# PLT-01-RevD.net
KiCad netlist of a schematic drawn in EAGLE
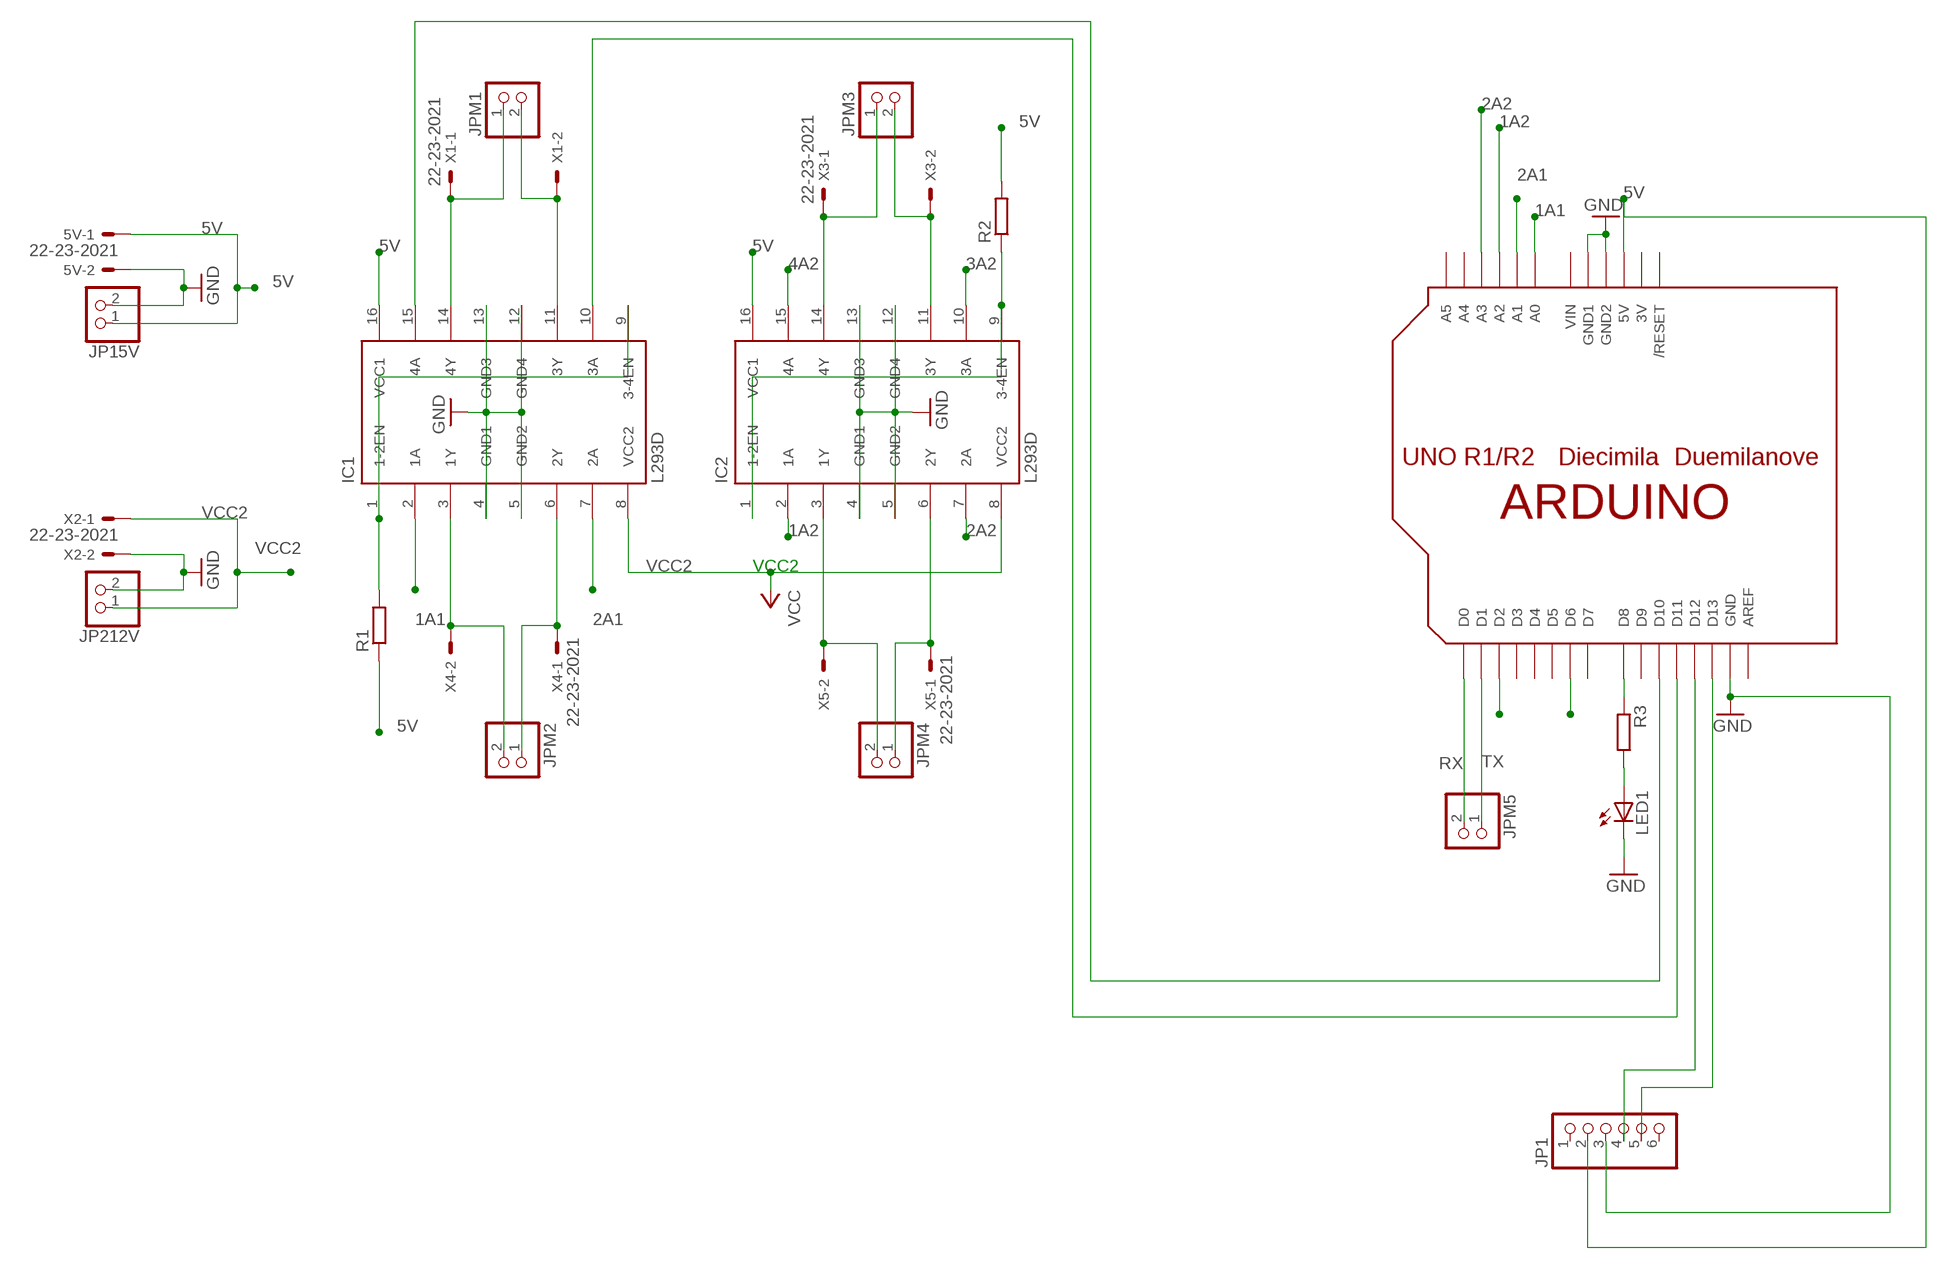
[diagram p0: schematic, sheet 1]

(export (version "E")
  (design (tool "Eeschema 10.0.6"))
  (components
    (comp (ref "5V")
      (value "22-23-2021")
      (footprint "eagle-import:22-23-2021")
      (fields (field (name "MF") "MOLEX"))
      (libsource (lib "eagle-import") (part "22-23-2021"))
    )
    (comp (ref "IC1")
      (value "L293D")
      (footprint "eagle-import:DIL16")
      (libsource (lib "eagle-import") (part "L293D"))
    )
    (comp (ref "IC2")
      (value "L293D")
      (footprint "eagle-import:DIL16")
      (libsource (lib "eagle-import") (part "L293D"))
    )
    (comp (ref "JP1")
      (value "PINHD-1X6")
      (footprint "eagle-import:1X06")
      (libsource (lib "eagle-import") (part "PINHD-1X6"))
    )
    (comp (ref "JP15V")
      (value "PINHD-1X2")
      (footprint "eagle-import:1X02")
      (libsource (lib "eagle-import") (part "PINHD-1X2"))
    )
    (comp (ref "JP212V")
      (value "PINHD-1X2")
      (footprint "eagle-import:1X02")
      (libsource (lib "eagle-import") (part "PINHD-1X2"))
    )
    (comp (ref "JPM1")
      (value "PINHD-1X2")
      (footprint "eagle-import:1X02")
      (libsource (lib "eagle-import") (part "PINHD-1X2"))
    )
    (comp (ref "JPM2")
      (value "PINHD-1X2")
      (footprint "eagle-import:1X02")
      (libsource (lib "eagle-import") (part "PINHD-1X2"))
    )
    (comp (ref "JPM3")
      (value "PINHD-1X2")
      (footprint "eagle-import:1X02")
      (libsource (lib "eagle-import") (part "PINHD-1X2"))
    )
    (comp (ref "JPM4")
      (value "PINHD-1X2")
      (footprint "eagle-import:1X02")
      (libsource (lib "eagle-import") (part "PINHD-1X2"))
    )
    (comp (ref "JPM5")
      (value "PINHD-1X2")
      (footprint "eagle-import:1X02")
      (libsource (lib "eagle-import") (part "PINHD-1X2"))
    )
    (comp (ref "LED1")
      (value "LED5MM")
      (footprint "eagle-import:LED5MM")
      (libsource (lib "eagle-import") (part "LED5MM"))
    )
    (comp (ref "R1")
      (value "R-EU_0207/10")
      (footprint "eagle-import:0207_10")
      (libsource (lib "eagle-import") (part "R-EU_0207/10"))
    )
    (comp (ref "R2")
      (value "R-EU_0207/10")
      (footprint "eagle-import:0207_10")
      (libsource (lib "eagle-import") (part "R-EU_0207/10"))
    )
    (comp (ref "R3")
      (value "R-EU_0207/10")
      (footprint "eagle-import:0207_10")
      (libsource (lib "eagle-import") (part "R-EU_0207/10"))
    )
    (comp (ref "U$1")
      (value "ARDUINOUNO")
      (footprint "eagle-import:ARDUINO")
      (libsource (lib "eagle-import") (part "ARDUINOUNO"))
    )
    (comp (ref "X1")
      (value "22-23-2021")
      (footprint "eagle-import:22-23-2021")
      (fields (field (name "MF") "MOLEX"))
      (libsource (lib "eagle-import") (part "22-23-2021"))
    )
    (comp (ref "X2")
      (value "22-23-2021")
      (footprint "eagle-import:22-23-2021")
      (fields (field (name "MF") "MOLEX"))
      (libsource (lib "eagle-import") (part "22-23-2021"))
    )
    (comp (ref "X3")
      (value "22-23-2021")
      (footprint "eagle-import:22-23-2021")
      (fields (field (name "MF") "MOLEX"))
      (libsource (lib "eagle-import") (part "22-23-2021"))
    )
    (comp (ref "X4")
      (value "22-23-2021")
      (footprint "eagle-import:22-23-2021")
      (fields (field (name "MF") "MOLEX"))
      (libsource (lib "eagle-import") (part "22-23-2021"))
    )
    (comp (ref "X5")
      (value "22-23-2021")
      (footprint "eagle-import:22-23-2021")
      (fields (field (name "MF") "MOLEX"))
      (libsource (lib "eagle-import") (part "22-23-2021"))
    )
  )
  (nets
    (net (code "1") (name "/1A1") (class "Default")
      (node (ref "IC1") (pin "2") (pinfunction "1A_2") (pintype "input"))
      (node (ref "U$1") (pin "A0") (pinfunction "A0_A0") (pintype "bidirectional"))
    )
    (net (code "2") (name "/1A2") (class "Default")
      (node (ref "IC2") (pin "2") (pinfunction "1A_2") (pintype "input"))
      (node (ref "U$1") (pin "A2") (pinfunction "A2_A2") (pintype "bidirectional"))
    )
    (net (code "3") (name "/2A1") (class "Default")
      (node (ref "IC1") (pin "7") (pinfunction "2A_7") (pintype "input"))
      (node (ref "U$1") (pin "A1") (pinfunction "A1_A1") (pintype "bidirectional"))
    )
    (net (code "4") (name "/2A2") (class "Default")
      (node (ref "IC2") (pin "7") (pinfunction "2A_7") (pintype "input"))
      (node (ref "U$1") (pin "A3") (pinfunction "A3_A3") (pintype "bidirectional"))
    )
    (net (code "5") (name "/3A2") (class "Default")
      (node (ref "IC2") (pin "10") (pinfunction "3A_10") (pintype "input"))
      (node (ref "U$1") (pin "D2") (pinfunction "D2_D2") (pintype "bidirectional"))
    )
    (net (code "6") (name "/3V") (class "Default")
      (node (ref "U$1") (pin "3V") (pinfunction "3V_3V") (pintype "power_in"))
    )
    (net (code "7") (name "/4A2") (class "Default")
      (node (ref "IC2") (pin "15") (pinfunction "4A_15") (pintype "input"))
      (node (ref "U$1") (pin "D6") (pinfunction "D6_D6") (pintype "bidirectional"))
    )
    (net (code "8") (name "/5V") (class "Default")
      (node (ref "5V") (pin "1") (pinfunction "S_1") (pintype "passive"))
      (node (ref "IC1") (pin "16") (pinfunction "VCC1_16") (pintype "power_in"))
      (node (ref "IC2") (pin "16") (pinfunction "VCC1_16") (pintype "power_in"))
      (node (ref "JP1") (pin "2") (pinfunction "2_2") (pintype "passive"))
      (node (ref "JP15V") (pin "1") (pinfunction "1_1") (pintype "passive"))
      (node (ref "R1") (pin "1") (pinfunction "1_1") (pintype "passive"))
      (node (ref "R2") (pin "2") (pinfunction "2_2") (pintype "passive"))
      (node (ref "U$1") (pin "5V") (pinfunction "5V_5V") (pintype "power_in"))
    )
    (net (code "9") (name "/RX") (class "Default")
      (node (ref "JPM5") (pin "2") (pinfunction "2_2") (pintype "passive"))
      (node (ref "U$1") (pin "D0") (pinfunction "D0_D0") (pintype "bidirectional"))
    )
    (net (code "10") (name "/TX") (class "Default")
      (node (ref "JPM5") (pin "1") (pinfunction "1_1") (pintype "passive"))
      (node (ref "U$1") (pin "D1") (pinfunction "D1_D1") (pintype "bidirectional"))
    )
    (net (code "11") (name "/VIN") (class "Default")
      (node (ref "U$1") (pin "VIN") (pinfunction "VIN_VIN") (pintype "power_in"))
    )
    (net (code "12") (name "GND") (class "Default")
      (node (ref "5V") (pin "2") (pinfunction "S_2") (pintype "passive"))
      (node (ref "IC1") (pin "12") (pinfunction "GND4_12") (pintype "power_in"))
      (node (ref "IC1") (pin "13") (pinfunction "GND3_13") (pintype "power_in"))
      (node (ref "IC1") (pin "4") (pinfunction "GND1_4") (pintype "power_in"))
      (node (ref "IC1") (pin "5") (pinfunction "GND2_5") (pintype "power_in"))
      (node (ref "IC2") (pin "12") (pinfunction "GND4_12") (pintype "power_in"))
      (node (ref "IC2") (pin "13") (pinfunction "GND3_13") (pintype "power_in"))
      (node (ref "IC2") (pin "4") (pinfunction "GND1_4") (pintype "power_in"))
      (node (ref "IC2") (pin "5") (pinfunction "GND2_5") (pintype "power_in"))
      (node (ref "JP1") (pin "3") (pinfunction "3_3") (pintype "passive"))
      (node (ref "JP15V") (pin "2") (pinfunction "2_2") (pintype "passive"))
      (node (ref "JP212V") (pin "2") (pinfunction "2_2") (pintype "passive"))
      (node (ref "LED1") (pin "K") (pinfunction "C_K") (pintype "passive"))
      (node (ref "U$1") (pin "GND") (pinfunction "GND_GND") (pintype "power_in"))
      (node (ref "U$1") (pin "GND1") (pinfunction "GND1_GND1") (pintype "power_in"))
      (node (ref "U$1") (pin "GND2") (pinfunction "GND2_GND2") (pintype "power_in"))
      (node (ref "X2") (pin "2") (pinfunction "S_2") (pintype "passive"))
    )
    (net (code "13") (name "Net-(IC1-1-2EN)") (class "Default")
      (node (ref "IC1") (pin "1") (pinfunction "1-2EN_1") (pintype "input"))
      (node (ref "IC1") (pin "9") (pinfunction "3-4EN_9") (pintype "input"))
      (node (ref "R1") (pin "2") (pinfunction "2_2") (pintype "passive"))
    )
    (net (code "14") (name "Net-(IC1-1Y)") (class "Default")
      (node (ref "IC1") (pin "3") (pinfunction "1Y_3") (pintype "output"))
      (node (ref "JPM2") (pin "2") (pinfunction "2_2") (pintype "passive"))
      (node (ref "X4") (pin "2") (pinfunction "S_2") (pintype "passive"))
    )
    (net (code "15") (name "Net-(IC1-2Y)") (class "Default")
      (node (ref "IC1") (pin "6") (pinfunction "2Y_6") (pintype "output"))
      (node (ref "JPM2") (pin "1") (pinfunction "1_1") (pintype "passive"))
      (node (ref "X4") (pin "1") (pinfunction "S_1") (pintype "passive"))
    )
    (net (code "16") (name "Net-(IC1-3A)") (class "Default")
      (node (ref "IC1") (pin "10") (pinfunction "3A_10") (pintype "input"))
      (node (ref "U$1") (pin "D11") (pinfunction "D11_D11") (pintype "bidirectional"))
    )
    (net (code "17") (name "Net-(IC1-3Y)") (class "Default")
      (node (ref "IC1") (pin "11") (pinfunction "3Y_11") (pintype "output"))
      (node (ref "JPM1") (pin "2") (pinfunction "2_2") (pintype "passive"))
      (node (ref "X1") (pin "2") (pinfunction "S_2") (pintype "passive"))
    )
    (net (code "18") (name "Net-(IC1-4A)") (class "Default")
      (node (ref "IC1") (pin "15") (pinfunction "4A_15") (pintype "input"))
      (node (ref "U$1") (pin "D10") (pinfunction "D10_D10") (pintype "bidirectional"))
    )
    (net (code "19") (name "Net-(IC1-4Y)") (class "Default")
      (node (ref "IC1") (pin "14") (pinfunction "4Y_14") (pintype "output"))
      (node (ref "JPM1") (pin "1") (pinfunction "1_1") (pintype "passive"))
      (node (ref "X1") (pin "1") (pinfunction "S_1") (pintype "passive"))
    )
    (net (code "20") (name "Net-(IC2-1-2EN)") (class "Default")
      (node (ref "IC2") (pin "1") (pinfunction "1-2EN_1") (pintype "input"))
      (node (ref "IC2") (pin "9") (pinfunction "3-4EN_9") (pintype "input"))
      (node (ref "R2") (pin "1") (pinfunction "1_1") (pintype "passive"))
    )
    (net (code "21") (name "Net-(IC2-1Y)") (class "Default")
      (node (ref "IC2") (pin "3") (pinfunction "1Y_3") (pintype "output"))
      (node (ref "JPM4") (pin "2") (pinfunction "2_2") (pintype "passive"))
      (node (ref "X5") (pin "2") (pinfunction "S_2") (pintype "passive"))
    )
    (net (code "22") (name "Net-(IC2-2Y)") (class "Default")
      (node (ref "IC2") (pin "6") (pinfunction "2Y_6") (pintype "output"))
      (node (ref "JPM4") (pin "1") (pinfunction "1_1") (pintype "passive"))
      (node (ref "X5") (pin "1") (pinfunction "S_1") (pintype "passive"))
    )
    (net (code "23") (name "Net-(IC2-3Y)") (class "Default")
      (node (ref "IC2") (pin "11") (pinfunction "3Y_11") (pintype "output"))
      (node (ref "JPM3") (pin "2") (pinfunction "2_2") (pintype "passive"))
      (node (ref "X3") (pin "2") (pinfunction "S_2") (pintype "passive"))
    )
    (net (code "24") (name "Net-(IC2-4Y)") (class "Default")
      (node (ref "IC2") (pin "14") (pinfunction "4Y_14") (pintype "output"))
      (node (ref "JPM3") (pin "1") (pinfunction "1_1") (pintype "passive"))
      (node (ref "X3") (pin "1") (pinfunction "S_1") (pintype "passive"))
    )
    (net (code "25") (name "Net-(JP1-Pad4)") (class "Default")
      (node (ref "JP1") (pin "4") (pinfunction "4_4") (pintype "passive"))
      (node (ref "U$1") (pin "D12") (pinfunction "D12_D12") (pintype "bidirectional"))
    )
    (net (code "26") (name "Net-(JP1-Pad5)") (class "Default")
      (node (ref "JP1") (pin "5") (pinfunction "5_5") (pintype "passive"))
      (node (ref "U$1") (pin "D13") (pinfunction "D13_D13") (pintype "bidirectional"))
    )
    (net (code "27") (name "Net-(LED1-PadA)") (class "Default")
      (node (ref "LED1") (pin "A") (pinfunction "A_A") (pintype "passive"))
      (node (ref "R3") (pin "2") (pinfunction "2_2") (pintype "passive"))
    )
    (net (code "28") (name "Net-(R3-Pad1)") (class "Default")
      (node (ref "R3") (pin "1") (pinfunction "1_1") (pintype "passive"))
      (node (ref "U$1") (pin "D8") (pinfunction "D8_D8") (pintype "bidirectional"))
    )
    (net (code "29") (name "VCC") (class "Default")
      (node (ref "IC1") (pin "8") (pinfunction "VCC2_8") (pintype "power_in"))
      (node (ref "IC2") (pin "8") (pinfunction "VCC2_8") (pintype "power_in"))
      (node (ref "JP212V") (pin "1") (pinfunction "1_1") (pintype "passive"))
      (node (ref "X2") (pin "1") (pinfunction "S_1") (pintype "passive"))
    )
    (net (code "30") (name "unconnected-(JP1-Pad1)") (class "Default")
      (node (ref "JP1") (pin "1") (pinfunction "1_1") (pintype "passive"))
    )
    (net (code "31") (name "unconnected-(JP1-Pad6)") (class "Default")
      (node (ref "JP1") (pin "6") (pinfunction "6_6") (pintype "passive"))
    )
    (net (code "32") (name "unconnected-(U$1-PadA4)") (class "Default")
      (node (ref "U$1") (pin "A4") (pinfunction "A4_A4") (pintype "bidirectional"))
    )
    (net (code "33") (name "unconnected-(U$1-PadA5)") (class "Default")
      (node (ref "U$1") (pin "A5") (pinfunction "A5_A5") (pintype "bidirectional"))
    )
    (net (code "34") (name "unconnected-(U$1-PadAREF)") (class "Default")
      (node (ref "U$1") (pin "AREF") (pinfunction "AREF_AREF") (pintype "bidirectional"))
    )
    (net (code "35") (name "unconnected-(U$1-PadD3)") (class "Default")
      (node (ref "U$1") (pin "D3") (pinfunction "D3_D3") (pintype "bidirectional"))
    )
    (net (code "36") (name "unconnected-(U$1-PadD4)") (class "Default")
      (node (ref "U$1") (pin "D4") (pinfunction "D4_D4") (pintype "bidirectional"))
    )
    (net (code "37") (name "unconnected-(U$1-PadD5)") (class "Default")
      (node (ref "U$1") (pin "D5") (pinfunction "D5_D5") (pintype "bidirectional"))
    )
    (net (code "38") (name "unconnected-(U$1-PadD7)") (class "Default")
      (node (ref "U$1") (pin "D7") (pinfunction "D7_D7") (pintype "bidirectional"))
    )
    (net (code "39") (name "unconnected-(U$1-PadD9)") (class "Default")
      (node (ref "U$1") (pin "D9") (pinfunction "D9_D9") (pintype "bidirectional"))
    )
    (net (code "40") (name "unconnected-(U$1-{slash}RESET-PadRESET)") (class "Default")
      (node (ref "U$1") (pin "RESET") (pinfunction "/RESET_RESET") (pintype "bidirectional"))
    )
  )
)
